# pca10036_sheet4_connectors.net
KiCad netlist of a schematic drawn in Altium Designer
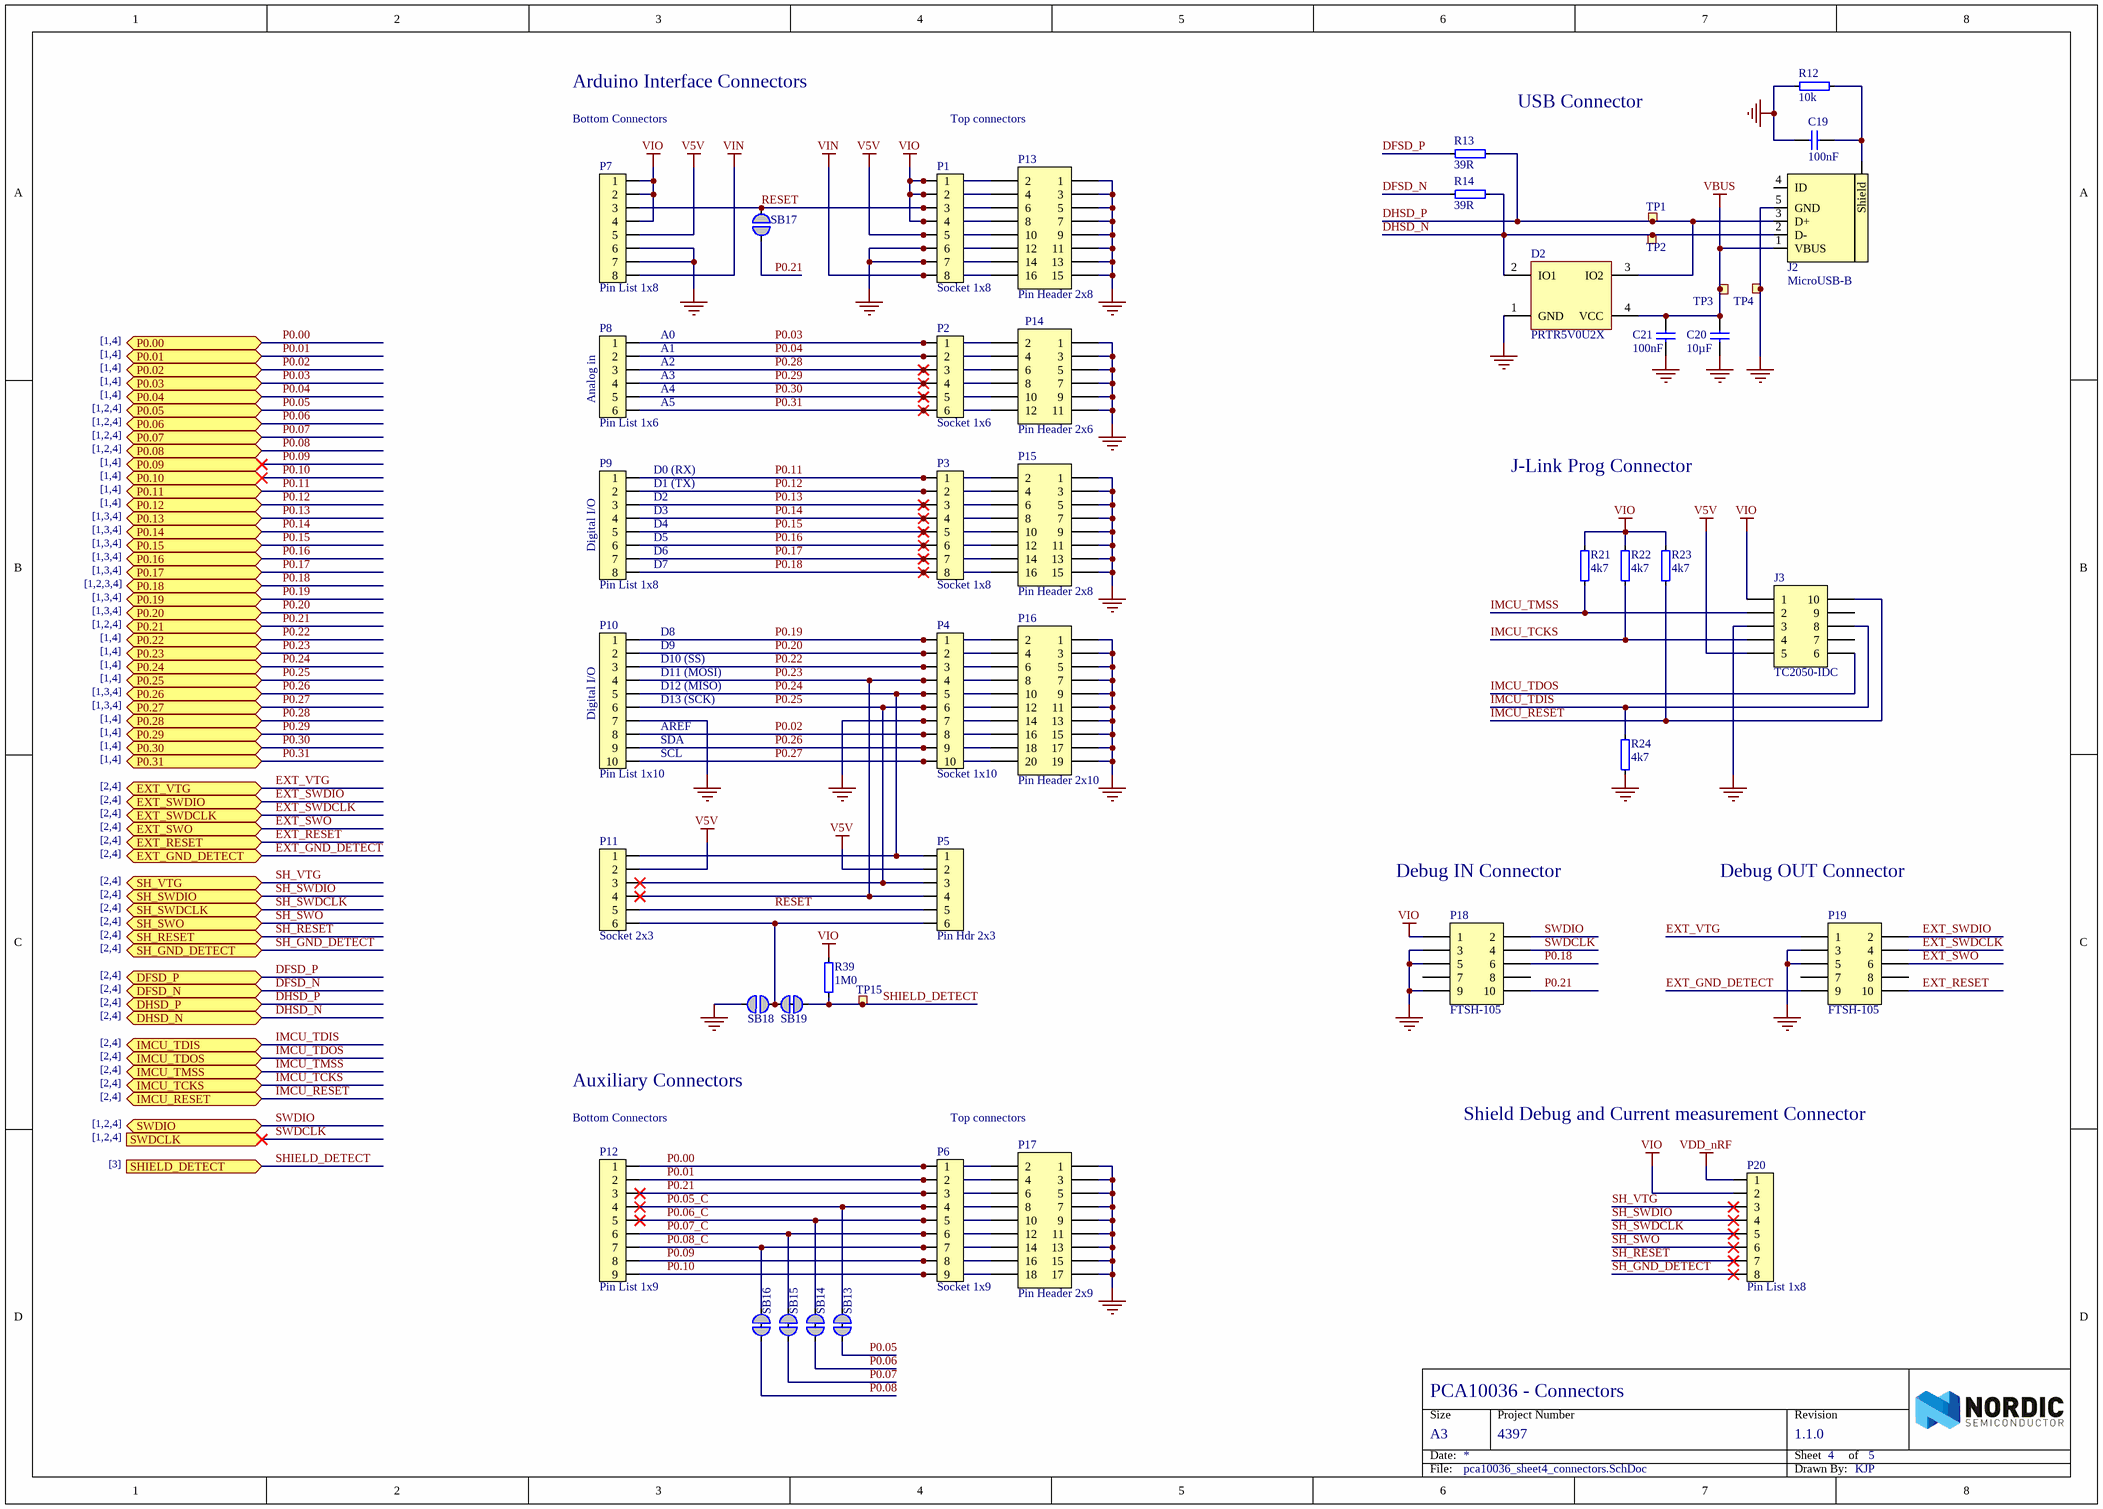
[diagram p0: pca10036_sheet4_connectors.SchDoc]

(export (version "E")
  (design (tool "Eeschema 10.0.6"))
  (components
    (comp (ref "C19")
      (value "100nF")
      (footprint "CAPC1005X04L")
      (description "Capacitor, X7R, ±10%")
      (fields (field (name "PART NUMBER") "C0402-100n") (field (name "PUBLISHER") "Nordic Semiconductor"))
      (libsource (lib "Nordic Passive DB") (part "CAP"))
    )
    (comp (ref "C20")
      (value "10µF")
      (footprint "CAPC1608X06L")
      (description "Capacitor, X5R, ±20%")
      (fields (field (name "PART NUMBER") "C0603-10µ") (field (name "PUBLISHER") "Nordic Semiconductor"))
      (libsource (lib "Nordic Passive DB") (part "CAP"))
    )
    (comp (ref "C21")
      (value "100nF")
      (footprint "CAPC1005X04L")
      (description "Capacitor, X7R, ±10%")
      (fields (field (name "PART NUMBER") "C0402-100n") (field (name "PUBLISHER") "Nordic Semiconductor"))
      (libsource (lib "Nordic Passive DB") (part "CAP"))
    )
    (comp (ref "D2")
      (value "PRTR5V0U2X")
      (footprint "SOT190P230X110-4L")
      (description "Ultra low capacitance double rail-to-rail ESD protection diode")
      (fields
        (field (name "MANUFACTURER") "NXP")
        (field (name "2ND SOURCE PART NUMBER") "152-4157")
        (field (name "PUBLISHER") "Nordic Semiconductor")
      )
      (libsource (lib "Nordic Discrete DB") (part "PRTR5V0U2X"))
    )
    (comp (ref "J2")
      (value "MicroUSB-B")
      (footprint "FCI_10118193-0001LF")
      (description "MicroUSB-B-SMT")
      (fields
        (field (name "PART NUMBER") "FCI 10118193-0001LF")
        (field (name "MANUFACTURER") "FCI")
        (field (name "PUBLISHER") "Nordic Semiconductor")
      )
      (libsource (lib "Nordic Passive DB") (part "MiniUSB-AB-SMT"))
    )
    (comp (ref "J3")
      (value "TC2050-IDC")
      (footprint "TC2050-IDC-NLFP")
      (description "CBL PLUG-OF-NAILS 10-PIN")
      (fields
        (field (name "PART NUMBER") "TC2050-IDC-NLFP")
        (field (name "MANUFACTURER") "Tag-Connect LLC")
        (field (name "PUBLISHER") "Nordic Semiconductor")
      )
      (libsource (lib "Nordic Passive DB") (part "CONN-2x5_var2"))
    )
    (comp (ref "P1")
      (value "Socket 1x8")
      (footprint "SOCKET_1x8_SMD")
      (description "Socket 1x8, 2.54mm (100mil), SMD")
      (fields
        (field (name "PART NUMBER") "Socket 1x8 SMD")
        (field (name "MANUFACTURER") "Samtec")
        (field (name "PUBLISHER") "Nordic Semiconductor")
      )
      (libsource (lib "") (part "CONN-8_1"))
    )
    (comp (ref "P2")
      (value "Socket 1x6")
      (footprint "SOCKET_1x6_SMD")
      (description "Socket 1x6, 2.54mm (100mil), SMD")
      (fields
        (field (name "PART NUMBER") "Socket 1x6 SMD")
        (field (name "MANUFACTURER") "Samtec")
        (field (name "PUBLISHER") "Nordic Semiconductor")
      )
      (libsource (lib "Nordic Passive DB") (part "CONN-6"))
    )
    (comp (ref "P3")
      (value "Socket 1x8")
      (footprint "SOCKET_1x8_SMD")
      (description "Socket 1x8, 2.54mm (100mil), SMD")
      (fields
        (field (name "PART NUMBER") "Socket 1x8 SMD")
        (field (name "MANUFACTURER") "Samtec")
        (field (name "PUBLISHER") "Nordic Semiconductor")
      )
      (libsource (lib "") (part "CONN-8_1"))
    )
    (comp (ref "P4")
      (value "Socket 1x10")
      (footprint "SOCKET_1x10_SMD")
      (description "Socket 1x10, 2.54mm (100mil), SMD")
      (fields
        (field (name "PART NUMBER") "Socket 1x10 SMD")
        (field (name "MANUFACTURER") "Samtec")
        (field (name "PUBLISHER") "Nordic Semiconductor")
      )
      (libsource (lib "Nordic Passive DB") (part "CONN-10"))
    )
    (comp (ref "P5")
      (value "Pin Hdr 2x3")
      (footprint "Molex 15-91-2060")
      (description "Pin Header 2x3, 2.54mm (100mil) SMD")
      (fields
        (field (name "PART NUMBER") "Pin Header 2x3 SMD")
        (field (name "MANUFACTURER") "Molex")
        (field (name "PUBLISHER") "Nordic Semiconductor")
      )
      (libsource (lib "Nordic Passive DB") (part "CONN-6"))
    )
    (comp (ref "P6")
      (value "Socket 1x9")
      (footprint "SOCKET_1x9_SMD")
      (description "Socket 1x9, 2.54mm (100mil), SMD")
      (fields
        (field (name "PART NUMBER") "Socket 1x9 SMD")
        (field (name "MANUFACTURER") "Samtec")
        (field (name "PUBLISHER") "Nordic Semiconductor")
      )
      (libsource (lib "") (part "CONN-9_1"))
    )
    (comp (ref "P7")
      (value "Pin List 1x8")
      (footprint "LIST_1x8_SMD")
      (description "Pin List 1x8, 2.54mm (100mil), SMD")
      (fields
        (field (name "PART NUMBER") "Pin List 1x8 SMD")
        (field (name "PUBLISHER") "Nordic Semiconductor")
      )
      (libsource (lib "Nordic Passive DB") (part "CONN-8"))
    )
    (comp (ref "P8")
      (value "Pin List 1x6")
      (footprint "LIST_1x6_SMD")
      (description "Pin List 1x6, 2.54mm (100mil), SMD")
      (fields
        (field (name "PART NUMBER") "Pin List 1x6 SMD")
        (field (name "PUBLISHER") "Nordic Semiconductor")
      )
      (libsource (lib "") (part "CONN-6_1"))
    )
    (comp (ref "P9")
      (value "Pin List 1x8")
      (footprint "LIST_1x8_SMD")
      (description "Pin List 1x8, 2.54mm (100mil), SMD")
      (fields
        (field (name "PART NUMBER") "Pin List 1x8 SMD")
        (field (name "PUBLISHER") "Nordic Semiconductor")
      )
      (libsource (lib "Nordic Passive DB") (part "CONN-8"))
    )
    (comp (ref "P10")
      (value "Pin List 1x10")
      (footprint "LIST_1x10_SMD")
      (description "Pin List 1x10, 2.54mm (100mil), SMD")
      (fields
        (field (name "PART NUMBER") "Pin List 1x10 SMD")
        (field (name "PUBLISHER") "Nordic Semiconductor")
      )
      (libsource (lib "") (part "CONN-10_1"))
    )
    (comp (ref "P11")
      (value "Socket 2x3")
      (footprint "SOCKET_2x3_SMD-2.54mm-bottom")
      (description "Socket 2x3, 2.54mm (100mil), SMD")
      (fields
        (field (name "PART NUMBER") "Socket 2x3 SMD Bottom")
        (field (name "MANUFACTURER") "Samtec")
        (field (name "PUBLISHER") "Nordic Semiconductor")
      )
      (libsource (lib "") (part "CONN-6_1"))
    )
    (comp (ref "P12")
      (value "Pin List 1x9")
      (footprint "LIST_1x9_SMD")
      (description "Pin List 1x9, 2.54mm (100mil), SMD")
      (fields
        (field (name "PART NUMBER") "Pin List 1x9 SMD")
        (field (name "PUBLISHER") "Nordic Semiconductor")
      )
      (libsource (lib "Nordic Passive DB") (part "CONN-9"))
    )
    (comp (ref "P13")
      (value "Pin Header 2x8")
      (footprint "HDR_2x8")
      (description "Pin Header 2x8, 2.54mm (100mil)")
      (fields (field (name "PUBLISHER") "Nordic Semiconductor"))
      (libsource (lib "Nordic Passive DB") (part "CONN-2x8"))
    )
    (comp (ref "P14")
      (value "Pin Header 2x6")
      (footprint "HDR_2x6")
      (description "Pin Header 2x6, 2.54mm (100mil)")
      (fields (field (name "PUBLISHER") "Nordic Semiconductor"))
      (libsource (lib "Nordic Passive DB") (part "CONN-2x6"))
    )
    (comp (ref "P15")
      (value "Pin Header 2x8")
      (footprint "HDR_2x8")
      (description "Pin Header 2x8, 2.54mm (100mil)")
      (fields (field (name "PUBLISHER") "Nordic Semiconductor"))
      (libsource (lib "Nordic Passive DB") (part "CONN-2x8"))
    )
    (comp (ref "P16")
      (value "Pin Header 2x10")
      (footprint "HDR_2x10")
      (description "Pin Header 2x10, 2.54mm (100mil)")
      (fields (field (name "PUBLISHER") "Nordic Semiconductor"))
      (libsource (lib "Nordic Passive DB") (part "CONN-2x10"))
    )
    (comp (ref "P17")
      (value "Pin Header 2x9")
      (footprint "HDR_2x9")
      (description "Pin Header 2x9, 2.54mm (100mil)")
      (fields (field (name "PUBLISHER") "Nordic Semiconductor"))
      (libsource (lib "Nordic Passive DB") (part "CONN-2x9"))
    )
    (comp (ref "P18")
      (value "FTSH-105")
      (footprint "FTSH-105-K")
      (description "SAMTEC - CONN HEADER 10POS DUAL .05\" SMD KEYING SHROUD")
      (fields
        (field (name "PART NUMBER") "Samtec FTSH-105 Keying Shroud")
        (field (name "MANUFACTURER") "Samtec")
        (field (name "PUBLISHER") "Nordic Semiconductor")
      )
      (libsource (lib "Nordic Passive DB") (part "CONN-2x5"))
    )
    (comp (ref "P19")
      (value "FTSH-105")
      (footprint "FTSH-105-K")
      (description "SAMTEC - CONN HEADER 10POS DUAL .05\" SMD KEYING SHROUD")
      (fields
        (field (name "PART NUMBER") "Samtec FTSH-105 Keying Shroud")
        (field (name "MANUFACTURER") "Samtec")
        (field (name "PUBLISHER") "Nordic Semiconductor")
      )
      (libsource (lib "Nordic Passive DB") (part "CONN-2x5"))
    )
    (comp (ref "P20")
      (value "Pin List 1x8")
      (footprint "LIST_1x8_SMD")
      (description "Pin List 1x8, 2.54mm (100mil), SMD")
      (fields
        (field (name "PART NUMBER") "Pin List 1x8 SMD")
        (field (name "PUBLISHER") "Nordic Semiconductor")
      )
      (libsource (lib "") (part "CONN-8_1"))
    )
    (comp (ref "R12")
      (value "10k")
      (footprint "RESC1005X04L")
      (description "Resistor, ±1%, 0.063W")
      (fields (field (name "PART NUMBER") "R0402-10k") (field (name "PUBLISHER") "Nordic Semiconductor"))
      (libsource (lib "Nordic Passive DB") (part "RES_1"))
    )
    (comp (ref "R13")
      (value "39R")
      (footprint "RESC1005X04L")
      (description "Resistor, ±1%, 0.063W")
      (fields (field (name "PART NUMBER") "R0402-39R") (field (name "PUBLISHER") "Nordic Semiconductor"))
      (libsource (lib "Nordic Passive DB") (part "RES_1"))
    )
    (comp (ref "R14")
      (value "39R")
      (footprint "RESC1005X04L")
      (description "Resistor, ±1%, 0.063W")
      (fields (field (name "PART NUMBER") "R0402-39R") (field (name "PUBLISHER") "Nordic Semiconductor"))
      (libsource (lib "Nordic Passive DB") (part "RES_1"))
    )
    (comp (ref "R21")
      (value "4k7")
      (footprint "RESC1005X04L")
      (description "Resistor, ±1%, 0.063W")
      (fields (field (name "PART NUMBER") "R0402-4k7") (field (name "PUBLISHER") "Nordic Semiconductor"))
      (libsource (lib "Nordic Passive DB") (part "RES_1"))
    )
    (comp (ref "R22")
      (value "4k7")
      (footprint "RESC1005X04L")
      (description "Resistor, ±1%, 0.063W")
      (fields (field (name "PART NUMBER") "R0402-4k7") (field (name "PUBLISHER") "Nordic Semiconductor"))
      (libsource (lib "Nordic Passive DB") (part "RES_1"))
    )
    (comp (ref "R23")
      (value "4k7")
      (footprint "RESC1005X04L")
      (description "Resistor, ±1%, 0.063W")
      (fields (field (name "PART NUMBER") "R0402-4k7") (field (name "PUBLISHER") "Nordic Semiconductor"))
      (libsource (lib "Nordic Passive DB") (part "RES_1"))
    )
    (comp (ref "R24")
      (value "4k7")
      (footprint "RESC1005X04L")
      (description "Resistor, ±1%, 0.063W")
      (fields (field (name "PART NUMBER") "R0402-4k7") (field (name "PUBLISHER") "Nordic Semiconductor"))
      (libsource (lib "Nordic Passive DB") (part "RES_1"))
    )
    (comp (ref "R39")
      (value "1M0")
      (footprint "RESC1005X04L")
      (description "Resistor, ±1%, 0.063W")
      (fields (field (name "PART NUMBER") "R0402-1M0") (field (name "PUBLISHER") "Nordic Semiconductor"))
      (libsource (lib "Nordic Passive DB") (part "RES_1"))
    )
    (comp (ref "SB13")
      (value "Solderbridge")
      (footprint "Solderbridge_Shorted")
      (description "Shorted Solderbridge")
      (fields
        (field (name "PART NUMBER") "Solderbridge Shorted")
        (field (name "PUBLISHER") "Nordic Semiconductor")
      )
      (libsource (lib "Nordic Passive DB") (part "SOLDERBRIDGE_SHORTED"))
    )
    (comp (ref "SB14")
      (value "Solderbridge")
      (footprint "Solderbridge_Shorted")
      (description "Shorted Solderbridge")
      (fields
        (field (name "PART NUMBER") "Solderbridge Shorted")
        (field (name "PUBLISHER") "Nordic Semiconductor")
      )
      (libsource (lib "Nordic Passive DB") (part "SOLDERBRIDGE_SHORTED"))
    )
    (comp (ref "SB15")
      (value "Solderbridge")
      (footprint "Solderbridge_Shorted")
      (description "Shorted Solderbridge")
      (fields
        (field (name "PART NUMBER") "Solderbridge Shorted")
        (field (name "PUBLISHER") "Nordic Semiconductor")
      )
      (libsource (lib "Nordic Passive DB") (part "SOLDERBRIDGE_SHORTED"))
    )
    (comp (ref "SB16")
      (value "Solderbridge")
      (footprint "Solderbridge_Shorted")
      (description "Shorted Solderbridge")
      (fields
        (field (name "PART NUMBER") "Solderbridge Shorted")
        (field (name "PUBLISHER") "Nordic Semiconductor")
      )
      (libsource (lib "Nordic Passive DB") (part "SOLDERBRIDGE_SHORTED"))
    )
    (comp (ref "SB17")
      (value "Solderbridge")
      (footprint "Solderbridge")
      (fields (field (name "PUBLISHER") "Nordic Semiconductor"))
      (libsource (lib "Nordic Passive DB") (part "SOLDERBRIDGE"))
    )
    (comp (ref "SB18")
      (value "Solderbridge")
      (footprint "Solderbridge")
      (fields (field (name "PUBLISHER") "Nordic Semiconductor"))
      (libsource (lib "Nordic Passive DB") (part "SOLDERBRIDGE"))
    )
    (comp (ref "SB19")
      (value "Solderbridge")
      (footprint "Solderbridge_Shorted")
      (description "Shorted Solderbridge")
      (fields
        (field (name "PART NUMBER") "Solderbridge Shorted")
        (field (name "PUBLISHER") "Nordic Semiconductor")
      )
      (libsource (lib "Nordic Passive DB") (part "SOLDERBRIDGE_SHORTED"))
    )
    (comp (ref "TP1")
      (value "Ø1.0mm,SMD")
      (footprint "TP_SMD_Ø1.0mm")
      (description "1.0mm circular SMD testpad")
      (fields
        (field (name "PART NUMBER") "TP_SMD_Ø1.0MM")
        (field (name "MANUFACTURER") "Nordic Semiconductor")
        (field (name "PUBLISHER") "Nordic Semiconductor")
      )
      (libsource (lib "") (part "TESTPAD_2"))
    )
    (comp (ref "TP2")
      (value "Ø1.0mm,SMD")
      (footprint "TP_SMD_Ø1.0mm")
      (description "1.0mm circular SMD testpad")
      (fields
        (field (name "PART NUMBER") "TP_SMD_Ø1.0MM")
        (field (name "MANUFACTURER") "Nordic Semiconductor")
        (field (name "PUBLISHER") "Nordic Semiconductor")
      )
      (libsource (lib "") (part "TESTPAD_1"))
    )
    (comp (ref "TP3")
      (value "Ø1.0mm,SMD")
      (footprint "TP_SMD_Ø1.0mm")
      (description "1.0mm circular SMD testpad")
      (fields
        (field (name "PART NUMBER") "TP_SMD_Ø1.0MM")
        (field (name "MANUFACTURER") "Nordic Semiconductor")
        (field (name "PUBLISHER") "Nordic Semiconductor")
      )
      (libsource (lib "") (part "TESTPAD_3"))
    )
    (comp (ref "TP4")
      (value "Ø1.0mm,SMD")
      (footprint "TP_SMD_Ø1.0mm")
      (description "1.0mm circular SMD testpad")
      (fields
        (field (name "PART NUMBER") "TP_SMD_Ø1.0MM")
        (field (name "MANUFACTURER") "Nordic Semiconductor")
        (field (name "PUBLISHER") "Nordic Semiconductor")
      )
      (libsource (lib "Nordic Passive DB") (part "TESTPAD"))
    )
    (comp (ref "TP15")
      (value "Ø1.0mm,SMD")
      (footprint "TP_SMD_Ø1.0mm")
      (description "1.0mm circular SMD testpad")
      (fields
        (field (name "PART NUMBER") "TP_SMD_Ø1.0MM")
        (field (name "MANUFACTURER") "Nordic Semiconductor")
        (field (name "PUBLISHER") "Nordic Semiconductor")
      )
      (libsource (lib "") (part "TESTPAD_2"))
    )
  )
  (nets
    (net (code "1") (name "/DFSD_N") (class "Default")
      (node (ref "R14") (pin "1") (pinfunction "1_1") (pintype "passive"))
    )
    (net (code "2") (name "/DFSD_P") (class "Default")
      (node (ref "R13") (pin "1") (pinfunction "1_1") (pintype "passive"))
    )
    (net (code "3") (name "/DHSD_N") (class "Default")
      (node (ref "D2") (pin "2") (pinfunction "IO1_2") (pintype "passive"))
      (node (ref "J2") (pin "2") (pinfunction "D-_2") (pintype "passive"))
      (node (ref "R14") (pin "2") (pinfunction "2_2") (pintype "passive"))
      (node (ref "TP2") (pin "1") (pinfunction "1_1") (pintype "passive"))
    )
    (net (code "4") (name "/DHSD_P") (class "Default")
      (node (ref "D2") (pin "3") (pinfunction "IO2_3") (pintype "passive"))
      (node (ref "J2") (pin "3") (pinfunction "D+_3") (pintype "passive"))
      (node (ref "R13") (pin "2") (pinfunction "2_2") (pintype "passive"))
      (node (ref "TP1") (pin "1") (pinfunction "1_1") (pintype "passive"))
    )
    (net (code "5") (name "/EXT_GND_DETECT") (class "Default")
      (node (ref "P19") (pin "9") (pinfunction "9_9") (pintype "passive"))
    )
    (net (code "6") (name "/EXT_RESET") (class "Default")
      (node (ref "P19") (pin "10") (pinfunction "10_10") (pintype "passive"))
    )
    (net (code "7") (name "/EXT_SWDCLK") (class "Default")
      (node (ref "P19") (pin "4") (pinfunction "4_4") (pintype "passive"))
    )
    (net (code "8") (name "/EXT_SWDIO") (class "Default")
      (node (ref "P19") (pin "2") (pinfunction "2_2") (pintype "passive"))
    )
    (net (code "9") (name "/EXT_SWO") (class "Default")
      (node (ref "P19") (pin "6") (pinfunction "6_6") (pintype "passive"))
    )
    (net (code "10") (name "/EXT_VTG") (class "Default")
      (node (ref "P19") (pin "1") (pinfunction "1_1") (pintype "passive"))
    )
    (net (code "11") (name "/IMCU_RESET") (class "Default")
      (node (ref "J3") (pin "10") (pinfunction "10_10") (pintype "passive"))
      (node (ref "R23") (pin "1") (pinfunction "1_1") (pintype "passive"))
    )
    (net (code "12") (name "/IMCU_TCKS") (class "Default")
      (node (ref "J3") (pin "4") (pinfunction "4_4") (pintype "passive"))
      (node (ref "R22") (pin "1") (pinfunction "1_1") (pintype "passive"))
    )
    (net (code "13") (name "/IMCU_TDIS") (class "Default")
      (node (ref "J3") (pin "8") (pinfunction "8_8") (pintype "passive"))
      (node (ref "R24") (pin "1") (pinfunction "1_1") (pintype "passive"))
    )
    (net (code "14") (name "/IMCU_TDOS") (class "Default")
      (node (ref "J3") (pin "6") (pinfunction "6_6") (pintype "passive"))
    )
    (net (code "15") (name "/IMCU_TMSS") (class "Default")
      (node (ref "J3") (pin "2") (pinfunction "2_2") (pintype "passive"))
      (node (ref "R21") (pin "1") (pinfunction "1_1") (pintype "passive"))
    )
    (net (code "16") (name "/P0.00") (class "Default")
      (node (ref "P12") (pin "1") (pinfunction "1_1") (pintype "passive"))
      (node (ref "P17") (pin "2") (pinfunction "2_2") (pintype "passive"))
      (node (ref "P6") (pin "1") (pinfunction "1_1") (pintype "passive"))
    )
    (net (code "17") (name "/P0.01") (class "Default")
      (node (ref "P12") (pin "2") (pinfunction "2_2") (pintype "passive"))
      (node (ref "P17") (pin "4") (pinfunction "4_4") (pintype "passive"))
      (node (ref "P6") (pin "2") (pinfunction "2_2") (pintype "passive"))
    )
    (net (code "18") (name "/P0.02") (class "Default")
      (node (ref "P10") (pin "8") (pinfunction "8_8") (pintype "passive"))
      (node (ref "P16") (pin "16") (pinfunction "16_16") (pintype "passive"))
      (node (ref "P4") (pin "8") (pinfunction "8_8") (pintype "passive"))
    )
    (net (code "19") (name "/P0.03") (class "Default")
      (node (ref "P14") (pin "2") (pinfunction "2_2") (pintype "passive"))
      (node (ref "P2") (pin "1") (pinfunction "1_1") (pintype "passive"))
      (node (ref "P8") (pin "1") (pinfunction "1_1") (pintype "passive"))
    )
    (net (code "20") (name "/P0.04") (class "Default")
      (node (ref "P14") (pin "4") (pinfunction "4_4") (pintype "passive"))
      (node (ref "P2") (pin "2") (pinfunction "2_2") (pintype "passive"))
      (node (ref "P8") (pin "2") (pinfunction "2_2") (pintype "passive"))
    )
    (net (code "21") (name "/P0.05") (class "Default")
      (node (ref "SB13") (pin "2") (pinfunction "1_2") (pintype "passive"))
    )
    (net (code "22") (name "/P0.05_C") (class "Default")
      (node (ref "P12") (pin "4") (pinfunction "4_4") (pintype "power_in"))
      (node (ref "P17") (pin "8") (pinfunction "8_8") (pintype "passive"))
      (node (ref "P6") (pin "4") (pinfunction "4_4") (pintype "power_in"))
      (node (ref "SB13") (pin "1") (pinfunction "0_1") (pintype "passive"))
    )
    (net (code "23") (name "/P0.06") (class "Default")
      (node (ref "SB14") (pin "2") (pinfunction "1_2") (pintype "passive"))
    )
    (net (code "24") (name "/P0.06_C") (class "Default")
      (node (ref "P12") (pin "5") (pinfunction "5_5") (pintype "power_in"))
      (node (ref "P17") (pin "10") (pinfunction "10_10") (pintype "passive"))
      (node (ref "P6") (pin "5") (pinfunction "5_5") (pintype "power_in"))
      (node (ref "SB14") (pin "1") (pinfunction "0_1") (pintype "passive"))
    )
    (net (code "25") (name "/P0.07") (class "Default")
      (node (ref "SB15") (pin "2") (pinfunction "1_2") (pintype "passive"))
    )
    (net (code "26") (name "/P0.07_C") (class "Default")
      (node (ref "P12") (pin "6") (pinfunction "6_6") (pintype "power_in"))
      (node (ref "P17") (pin "12") (pinfunction "12_12") (pintype "passive"))
      (node (ref "P6") (pin "6") (pinfunction "6_6") (pintype "power_in"))
      (node (ref "SB15") (pin "1") (pinfunction "0_1") (pintype "passive"))
    )
    (net (code "27") (name "/P0.08") (class "Default")
      (node (ref "SB16") (pin "2") (pinfunction "1_2") (pintype "passive"))
    )
    (net (code "28") (name "/P0.08_C") (class "Default")
      (node (ref "P12") (pin "7") (pinfunction "7_7") (pintype "power_in"))
      (node (ref "P17") (pin "14") (pinfunction "14_14") (pintype "passive"))
      (node (ref "P6") (pin "7") (pinfunction "7_7") (pintype "power_in"))
      (node (ref "SB16") (pin "1") (pinfunction "0_1") (pintype "passive"))
    )
    (net (code "29") (name "/P0.09") (class "Default")
      (node (ref "P12") (pin "8") (pinfunction "8_8") (pintype "power_in"))
      (node (ref "P17") (pin "16") (pinfunction "16_16") (pintype "passive"))
      (node (ref "P6") (pin "8") (pinfunction "8_8") (pintype "power_in"))
    )
    (net (code "30") (name "/P0.10") (class "Default")
      (node (ref "P12") (pin "9") (pinfunction "9_9") (pintype "power_in"))
      (node (ref "P17") (pin "18") (pinfunction "18_18") (pintype "passive"))
      (node (ref "P6") (pin "9") (pinfunction "9_9") (pintype "power_in"))
    )
    (net (code "31") (name "/P0.11") (class "Default")
      (node (ref "P15") (pin "2") (pinfunction "2_2") (pintype "passive"))
      (node (ref "P3") (pin "1") (pinfunction "1_1") (pintype "passive"))
      (node (ref "P9") (pin "1") (pinfunction "1_1") (pintype "passive"))
    )
    (net (code "32") (name "/P0.12") (class "Default")
      (node (ref "P15") (pin "4") (pinfunction "4_4") (pintype "passive"))
      (node (ref "P3") (pin "2") (pinfunction "2_2") (pintype "passive"))
      (node (ref "P9") (pin "2") (pinfunction "2_2") (pintype "passive"))
    )
    (net (code "33") (name "/P0.13") (class "Default")
      (node (ref "P15") (pin "6") (pinfunction "6_6") (pintype "passive"))
      (node (ref "P3") (pin "3") (pinfunction "3_3") (pintype "power_in"))
      (node (ref "P9") (pin "3") (pinfunction "3_3") (pintype "power_in"))
    )
    (net (code "34") (name "/P0.14") (class "Default")
      (node (ref "P15") (pin "8") (pinfunction "8_8") (pintype "passive"))
      (node (ref "P3") (pin "4") (pinfunction "4_4") (pintype "power_in"))
      (node (ref "P9") (pin "4") (pinfunction "4_4") (pintype "power_in"))
    )
    (net (code "35") (name "/P0.15") (class "Default")
      (node (ref "P15") (pin "10") (pinfunction "10_10") (pintype "passive"))
      (node (ref "P3") (pin "5") (pinfunction "5_5") (pintype "power_in"))
      (node (ref "P9") (pin "5") (pinfunction "5_5") (pintype "power_in"))
    )
    (net (code "36") (name "/P0.16") (class "Default")
      (node (ref "P15") (pin "12") (pinfunction "12_12") (pintype "passive"))
      (node (ref "P3") (pin "6") (pinfunction "6_6") (pintype "power_in"))
      (node (ref "P9") (pin "6") (pinfunction "6_6") (pintype "power_in"))
    )
    (net (code "37") (name "/P0.17") (class "Default")
      (node (ref "P15") (pin "14") (pinfunction "14_14") (pintype "passive"))
      (node (ref "P3") (pin "7") (pinfunction "7_7") (pintype "power_in"))
      (node (ref "P9") (pin "7") (pinfunction "7_7") (pintype "power_in"))
    )
    (net (code "38") (name "/P0.18") (class "Default")
      (node (ref "P15") (pin "16") (pinfunction "16_16") (pintype "passive"))
      (node (ref "P18") (pin "6") (pinfunction "6_6") (pintype "passive"))
      (node (ref "P3") (pin "8") (pinfunction "8_8") (pintype "power_in"))
      (node (ref "P9") (pin "8") (pinfunction "8_8") (pintype "power_in"))
    )
    (net (code "39") (name "/P0.19") (class "Default")
      (node (ref "P10") (pin "1") (pinfunction "1_1") (pintype "passive"))
      (node (ref "P16") (pin "2") (pinfunction "2_2") (pintype "passive"))
      (node (ref "P4") (pin "1") (pinfunction "1_1") (pintype "passive"))
    )
    (net (code "40") (name "/P0.20") (class "Default")
      (node (ref "P10") (pin "2") (pinfunction "2_2") (pintype "passive"))
      (node (ref "P16") (pin "4") (pinfunction "4_4") (pintype "passive"))
      (node (ref "P4") (pin "2") (pinfunction "2_2") (pintype "passive"))
    )
    (net (code "41") (name "/P0.21") (class "Default")
      (node (ref "P12") (pin "3") (pinfunction "3_3") (pintype "power_in"))
      (node (ref "P17") (pin "6") (pinfunction "6_6") (pintype "passive"))
      (node (ref "P18") (pin "10") (pinfunction "10_10") (pintype "passive"))
      (node (ref "P6") (pin "3") (pinfunction "3_3") (pintype "power_in"))
      (node (ref "SB17") (pin "2") (pinfunction "1_2") (pintype "passive"))
    )
    (net (code "42") (name "/P0.22") (class "Default")
      (node (ref "P10") (pin "3") (pinfunction "3_3") (pintype "passive"))
      (node (ref "P16") (pin "6") (pinfunction "6_6") (pintype "passive"))
      (node (ref "P4") (pin "3") (pinfunction "3_3") (pintype "passive"))
    )
    (net (code "43") (name "/P0.23") (class "Default")
      (node (ref "P10") (pin "4") (pinfunction "4_4") (pintype "passive"))
      (node (ref "P11") (pin "4") (pinfunction "4_4") (pintype "power_in"))
      (node (ref "P16") (pin "8") (pinfunction "8_8") (pintype "passive"))
      (node (ref "P4") (pin "4") (pinfunction "4_4") (pintype "passive"))
      (node (ref "P5") (pin "4") (pinfunction "4_4") (pintype "power_in"))
    )
    (net (code "44") (name "/P0.24") (class "Default")
      (node (ref "P10") (pin "5") (pinfunction "5_5") (pintype "passive"))
      (node (ref "P11") (pin "1") (pinfunction "1_1") (pintype "passive"))
      (node (ref "P16") (pin "10") (pinfunction "10_10") (pintype "passive"))
      (node (ref "P4") (pin "5") (pinfunction "5_5") (pintype "passive"))
      (node (ref "P5") (pin "1") (pinfunction "1_1") (pintype "passive"))
    )
    (net (code "45") (name "/P0.25") (class "Default")
      (node (ref "P10") (pin "6") (pinfunction "6_6") (pintype "passive"))
      (node (ref "P11") (pin "3") (pinfunction "3_3") (pintype "power_in"))
      (node (ref "P16") (pin "12") (pinfunction "12_12") (pintype "passive"))
      (node (ref "P4") (pin "6") (pinfunction "6_6") (pintype "passive"))
      (node (ref "P5") (pin "3") (pinfunction "3_3") (pintype "power_in"))
    )
    (net (code "46") (name "/P0.26") (class "Default")
      (node (ref "P10") (pin "9") (pinfunction "9_9") (pintype "passive"))
      (node (ref "P16") (pin "18") (pinfunction "18_18") (pintype "passive"))
      (node (ref "P4") (pin "9") (pinfunction "9_9") (pintype "passive"))
    )
    (net (code "47") (name "/P0.27") (class "Default")
      (node (ref "P10") (pin "10") (pinfunction "10_10") (pintype "passive"))
      (node (ref "P16") (pin "20") (pinfunction "20_20") (pintype "passive"))
      (node (ref "P4") (pin "10") (pinfunction "10_10") (pintype "passive"))
    )
    (net (code "48") (name "/P0.28") (class "Default")
      (node (ref "P14") (pin "6") (pinfunction "6_6") (pintype "passive"))
      (node (ref "P2") (pin "3") (pinfunction "3_3") (pintype "power_in"))
      (node (ref "P8") (pin "3") (pinfunction "3_3") (pintype "power_in"))
    )
    (net (code "49") (name "/P0.29") (class "Default")
      (node (ref "P14") (pin "8") (pinfunction "8_8") (pintype "passive"))
      (node (ref "P2") (pin "4") (pinfunction "4_4") (pintype "power_in"))
      (node (ref "P8") (pin "4") (pinfunction "4_4") (pintype "power_in"))
    )
    (net (code "50") (name "/P0.30") (class "Default")
      (node (ref "P14") (pin "10") (pinfunction "10_10") (pintype "passive"))
      (node (ref "P2") (pin "5") (pinfunction "5_5") (pintype "power_in"))
      (node (ref "P8") (pin "5") (pinfunction "5_5") (pintype "power_in"))
    )
    (net (code "51") (name "/P0.31") (class "Default")
      (node (ref "P14") (pin "12") (pinfunction "12_12") (pintype "passive"))
      (node (ref "P2") (pin "6") (pinfunction "6_6") (pintype "power_in"))
      (node (ref "P8") (pin "6") (pinfunction "6_6") (pintype "power_in"))
    )
    (net (code "52") (name "/RESET") (class "Default")
      (node (ref "P1") (pin "3") (pinfunction "3_3") (pintype "power_in"))
      (node (ref "P11") (pin "5") (pinfunction "5_5") (pintype "power_in"))
      (node (ref "P13") (pin "6") (pinfunction "6_6") (pintype "passive"))
      (node (ref "P5") (pin "5") (pinfunction "5_5") (pintype "power_in"))
      (node (ref "P7") (pin "3") (pinfunction "3_3") (pintype "power_in"))
      (node (ref "SB17") (pin "1") (pinfunction "0_1") (pintype "passive"))
    )
    (net (code "53") (name "/SHIELD_DETECT") (class "Default")
      (node (ref "R39") (pin "1") (pinfunction "1_1") (pintype "passive"))
      (node (ref "SB19") (pin "2") (pinfunction "1_2") (pintype "passive"))
      (node (ref "TP15") (pin "1") (pinfunction "1_1") (pintype "passive"))
    )
    (net (code "54") (name "/SH_GND_DETECT") (class "Default")
      (node (ref "P20") (pin "8") (pinfunction "8_8") (pintype "power_in+no_connect"))
    )
    (net (code "55") (name "/SH_RESET") (class "Default")
      (node (ref "P20") (pin "7") (pinfunction "7_7") (pintype "power_in+no_connect"))
    )
    (net (code "56") (name "/SH_SWDCLK") (class "Default")
      (node (ref "P20") (pin "5") (pinfunction "5_5") (pintype "power_in+no_connect"))
    )
    (net (code "57") (name "/SH_SWDIO") (class "Default")
      (node (ref "P20") (pin "4") (pinfunction "4_4") (pintype "power_in+no_connect"))
    )
    (net (code "58") (name "/SH_SWO") (class "Default")
      (node (ref "P20") (pin "6") (pinfunction "6_6") (pintype "power_in+no_connect"))
    )
    (net (code "59") (name "/SH_VTG") (class "Default")
      (node (ref "P20") (pin "3") (pinfunction "3_3") (pintype "power_in+no_connect"))
    )
    (net (code "60") (name "/SWDCLK") (class "Default")
      (node (ref "P18") (pin "4") (pinfunction "4_4") (pintype "passive"))
    )
    (net (code "61") (name "/SWDIO") (class "Default")
      (node (ref "P18") (pin "2") (pinfunction "2_2") (pintype "passive"))
    )
    (net (code "62") (name "GND") (class "Default")
      (node (ref "C19") (pin "1") (pinfunction "1_1") (pintype "passive"))
      (node (ref "C20") (pin "1") (pinfunction "1_1") (pintype "passive"))
      (node (ref "C21") (pin "1") (pinfunction "1_1") (pintype "passive"))
      (node (ref "D2") (pin "1") (pinfunction "GND_1") (pintype "passive"))
      (node (ref "J2") (pin "5") (pinfunction "GND_5") (pintype "power_in"))
      (node (ref "J3") (pin "3") (pinfunction "3_3") (pintype "passive"))
      (node (ref "P1") (pin "6") (pinfunction "6_6") (pintype "power_in"))
      (node (ref "P1") (pin "7") (pinfunction "7_7") (pintype "power_in"))
      (node (ref "P10") (pin "7") (pinfunction "7_7") (pintype "passive"))
      (node (ref "P13") (pin "1") (pinfunction "1_1") (pintype "passive"))
      (node (ref "P13") (pin "11") (pinfunction "11_11") (pintype "passive"))
      (node (ref "P13") (pin "12") (pinfunction "12_12") (pintype "passive"))
      (node (ref "P13") (pin "13") (pinfunction "13_13") (pintype "passive"))
      (node (ref "P13") (pin "14") (pinfunction "14_14") (pintype "passive"))
      (node (ref "P13") (pin "15") (pinfunction "15_15") (pintype "passive"))
      (node (ref "P13") (pin "3") (pinfunction "3_3") (pintype "passive"))
      (node (ref "P13") (pin "5") (pinfunction "5_5") (pintype "passive"))
      (node (ref "P13") (pin "7") (pinfunction "7_7") (pintype "passive"))
      (node (ref "P13") (pin "9") (pinfunction "9_9") (pintype "passive"))
      (node (ref "P14") (pin "1") (pinfunction "1_1") (pintype "passive"))
      (node (ref "P14") (pin "11") (pinfunction "11_11") (pintype "passive"))
      (node (ref "P14") (pin "3") (pinfunction "3_3") (pintype "passive"))
      (node (ref "P14") (pin "5") (pinfunction "5_5") (pintype "passive"))
      (node (ref "P14") (pin "7") (pinfunction "7_7") (pintype "passive"))
      (node (ref "P14") (pin "9") (pinfunction "9_9") (pintype "passive"))
      (node (ref "P15") (pin "1") (pinfunction "1_1") (pintype "passive"))
      (node (ref "P15") (pin "11") (pinfunction "11_11") (pintype "passive"))
      (node (ref "P15") (pin "13") (pinfunction "13_13") (pintype "passive"))
      (node (ref "P15") (pin "15") (pinfunction "15_15") (pintype "passive"))
      (node (ref "P15") (pin "3") (pinfunction "3_3") (pintype "passive"))
      (node (ref "P15") (pin "5") (pinfunction "5_5") (pintype "passive"))
      (node (ref "P15") (pin "7") (pinfunction "7_7") (pintype "passive"))
      (node (ref "P15") (pin "9") (pinfunction "9_9") (pintype "passive"))
      (node (ref "P16") (pin "1") (pinfunction "1_1") (pintype "passive"))
      (node (ref "P16") (pin "11") (pinfunction "11_11") (pintype "passive"))
      (node (ref "P16") (pin "13") (pinfunction "13_13") (pintype "passive"))
      (node (ref "P16") (pin "14") (pinfunction "14_14") (pintype "passive"))
      (node (ref "P16") (pin "15") (pinfunction "15_15") (pintype "passive"))
      (node (ref "P16") (pin "17") (pinfunction "17_17") (pintype "passive"))
      (node (ref "P16") (pin "19") (pinfunction "19_19") (pintype "passive"))
      (node (ref "P16") (pin "3") (pinfunction "3_3") (pintype "passive"))
      (node (ref "P16") (pin "5") (pinfunction "5_5") (pintype "passive"))
      (node (ref "P16") (pin "7") (pinfunction "7_7") (pintype "passive"))
      (node (ref "P16") (pin "9") (pinfunction "9_9") (pintype "passive"))
      (node (ref "P17") (pin "1") (pinfunction "1_1") (pintype "passive"))
      (node (ref "P17") (pin "11") (pinfunction "11_11") (pintype "passive"))
      (node (ref "P17") (pin "13") (pinfunction "13_13") (pintype "passive"))
      (node (ref "P17") (pin "15") (pinfunction "15_15") (pintype "passive"))
      (node (ref "P17") (pin "17") (pinfunction "17_17") (pintype "passive"))
      (node (ref "P17") (pin "3") (pinfunction "3_3") (pintype "passive"))
      (node (ref "P17") (pin "5") (pinfunction "5_5") (pintype "passive"))
      (node (ref "P17") (pin "7") (pinfunction "7_7") (pintype "passive"))
      (node (ref "P17") (pin "9") (pinfunction "9_9") (pintype "passive"))
      (node (ref "P18") (pin "3") (pinfunction "3_3") (pintype "passive"))
      (node (ref "P18") (pin "5") (pinfunction "5_5") (pintype "passive"))
      (node (ref "P18") (pin "9") (pinfunction "9_9") (pintype "passive"))
      (node (ref "P19") (pin "3") (pinfunction "3_3") (pintype "passive"))
      (node (ref "P19") (pin "5") (pinfunction "5_5") (pintype "passive"))
      (node (ref "P4") (pin "7") (pinfunction "7_7") (pintype "passive"))
      (node (ref "P7") (pin "6") (pinfunction "6_6") (pintype "power_in"))
      (node (ref "P7") (pin "7") (pinfunction "7_7") (pintype "power_in"))
      (node (ref "R12") (pin "1") (pinfunction "1_1") (pintype "passive"))
      (node (ref "R24") (pin "2") (pinfunction "2_2") (pintype "passive"))
      (node (ref "SB18") (pin "1") (pinfunction "0_1") (pintype "passive"))
      (node (ref "TP4") (pin "1") (pinfunction "1_1") (pintype "passive"))
    )
    (net (code "63") (name "Net-(J2-Shield)") (class "Default")
      (node (ref "C19") (pin "2") (pinfunction "2_2") (pintype "passive"))
      (node (ref "J2") (pin "6") (pinfunction "Shield_6") (pintype "power_in"))
      (node (ref "R12") (pin "2") (pinfunction "2_2") (pintype "passive"))
    )
    (net (code "64") (name "Net-(SB18-1)") (class "Default")
      (node (ref "P11") (pin "6") (pinfunction "6_6") (pintype "power_in"))
      (node (ref "P5") (pin "6") (pinfunction "6_6") (pintype "power_in"))
      (node (ref "SB18") (pin "2") (pinfunction "1_2") (pintype "passive"))
      (node (ref "SB19") (pin "1") (pinfunction "0_1") (pintype "passive"))
    )
    (net (code "65") (name "V5V") (class "Default")
      (node (ref "J3") (pin "5") (pinfunction "5_5") (pintype "passive"))
      (node (ref "P1") (pin "5") (pinfunction "5_5") (pintype "power_in"))
      (node (ref "P11") (pin "2") (pinfunction "2_2") (pintype "passive"))
      (node (ref "P13") (pin "10") (pinfunction "10_10") (pintype "passive"))
      (node (ref "P5") (pin "2") (pinfunction "2_2") (pintype "passive"))
      (node (ref "P7") (pin "5") (pinfunction "5_5") (pintype "power_in"))
    )
    (net (code "66") (name "VBUS") (class "Default")
      (node (ref "C20") (pin "2") (pinfunction "2_2") (pintype "passive"))
      (node (ref "C21") (pin "2") (pinfunction "2_2") (pintype "passive"))
      (node (ref "D2") (pin "4") (pinfunction "VCC_4") (pintype "passive"))
      (node (ref "J2") (pin "1") (pinfunction "VBUS_1") (pintype "power_in"))
      (node (ref "TP3") (pin "1") (pinfunction "1_1") (pintype "passive"))
    )
    (net (code "67") (name "VDD_nRF") (class "Default")
      (node (ref "P20") (pin "1") (pinfunction "1_1") (pintype "passive"))
    )
    (net (code "68") (name "VIN") (class "Default")
      (node (ref "P1") (pin "8") (pinfunction "8_8") (pintype "power_in"))
      (node (ref "P13") (pin "16") (pinfunction "16_16") (pintype "passive"))
      (node (ref "P7") (pin "8") (pinfunction "8_8") (pintype "power_in"))
    )
    (net (code "69") (name "VIO") (class "Default")
      (node (ref "J3") (pin "1") (pinfunction "1_1") (pintype "passive"))
      (node (ref "P1") (pin "1") (pinfunction "1_1") (pintype "passive"))
      (node (ref "P1") (pin "2") (pinfunction "2_2") (pintype "passive"))
      (node (ref "P1") (pin "4") (pinfunction "4_4") (pintype "power_in"))
      (node (ref "P13") (pin "2") (pinfunction "2_2") (pintype "passive"))
      (node (ref "P13") (pin "4") (pinfunction "4_4") (pintype "passive"))
      (node (ref "P13") (pin "8") (pinfunction "8_8") (pintype "passive"))
      (node (ref "P18") (pin "1") (pinfunction "1_1") (pintype "passive"))
      (node (ref "P20") (pin "2") (pinfunction "2_2") (pintype "passive"))
      (node (ref "P7") (pin "1") (pinfunction "1_1") (pintype "passive"))
      (node (ref "P7") (pin "2") (pinfunction "2_2") (pintype "passive"))
      (node (ref "P7") (pin "4") (pinfunction "4_4") (pintype "power_in"))
      (node (ref "R21") (pin "2") (pinfunction "2_2") (pintype "passive"))
      (node (ref "R22") (pin "2") (pinfunction "2_2") (pintype "passive"))
      (node (ref "R23") (pin "2") (pinfunction "2_2") (pintype "passive"))
      (node (ref "R39") (pin "2") (pinfunction "2_2") (pintype "passive"))
    )
    (net (code "70") (name "unconnected-(J2-ID-Pad4)") (class "Default")
      (node (ref "J2") (pin "4") (pinfunction "ID_4") (pintype "passive"))
    )
    (net (code "71") (name "unconnected-(J3-Pad7)") (class "Default")
      (node (ref "J3") (pin "7") (pinfunction "7_7") (pintype "passive"))
    )
    (net (code "72") (name "unconnected-(J3-Pad9)") (class "Default")
      (node (ref "J3") (pin "9") (pinfunction "9_9") (pintype "passive"))
    )
    (net (code "73") (name "unconnected-(P18-Pad7)") (class "Default")
      (node (ref "P18") (pin "7") (pinfunction "7_7") (pintype "passive"))
    )
    (net (code "74") (name "unconnected-(P18-Pad8)") (class "Default")
      (node (ref "P18") (pin "8") (pinfunction "8_8") (pintype "passive"))
    )
    (net (code "75") (name "unconnected-(P19-Pad7)") (class "Default")
      (node (ref "P19") (pin "7") (pinfunction "7_7") (pintype "passive"))
    )
    (net (code "76") (name "unconnected-(P19-Pad8)") (class "Default")
      (node (ref "P19") (pin "8") (pinfunction "8_8") (pintype "passive"))
    )
  )
)
